# Base_Block.net
KiCad netlist of a schematic drawn in EAGLE
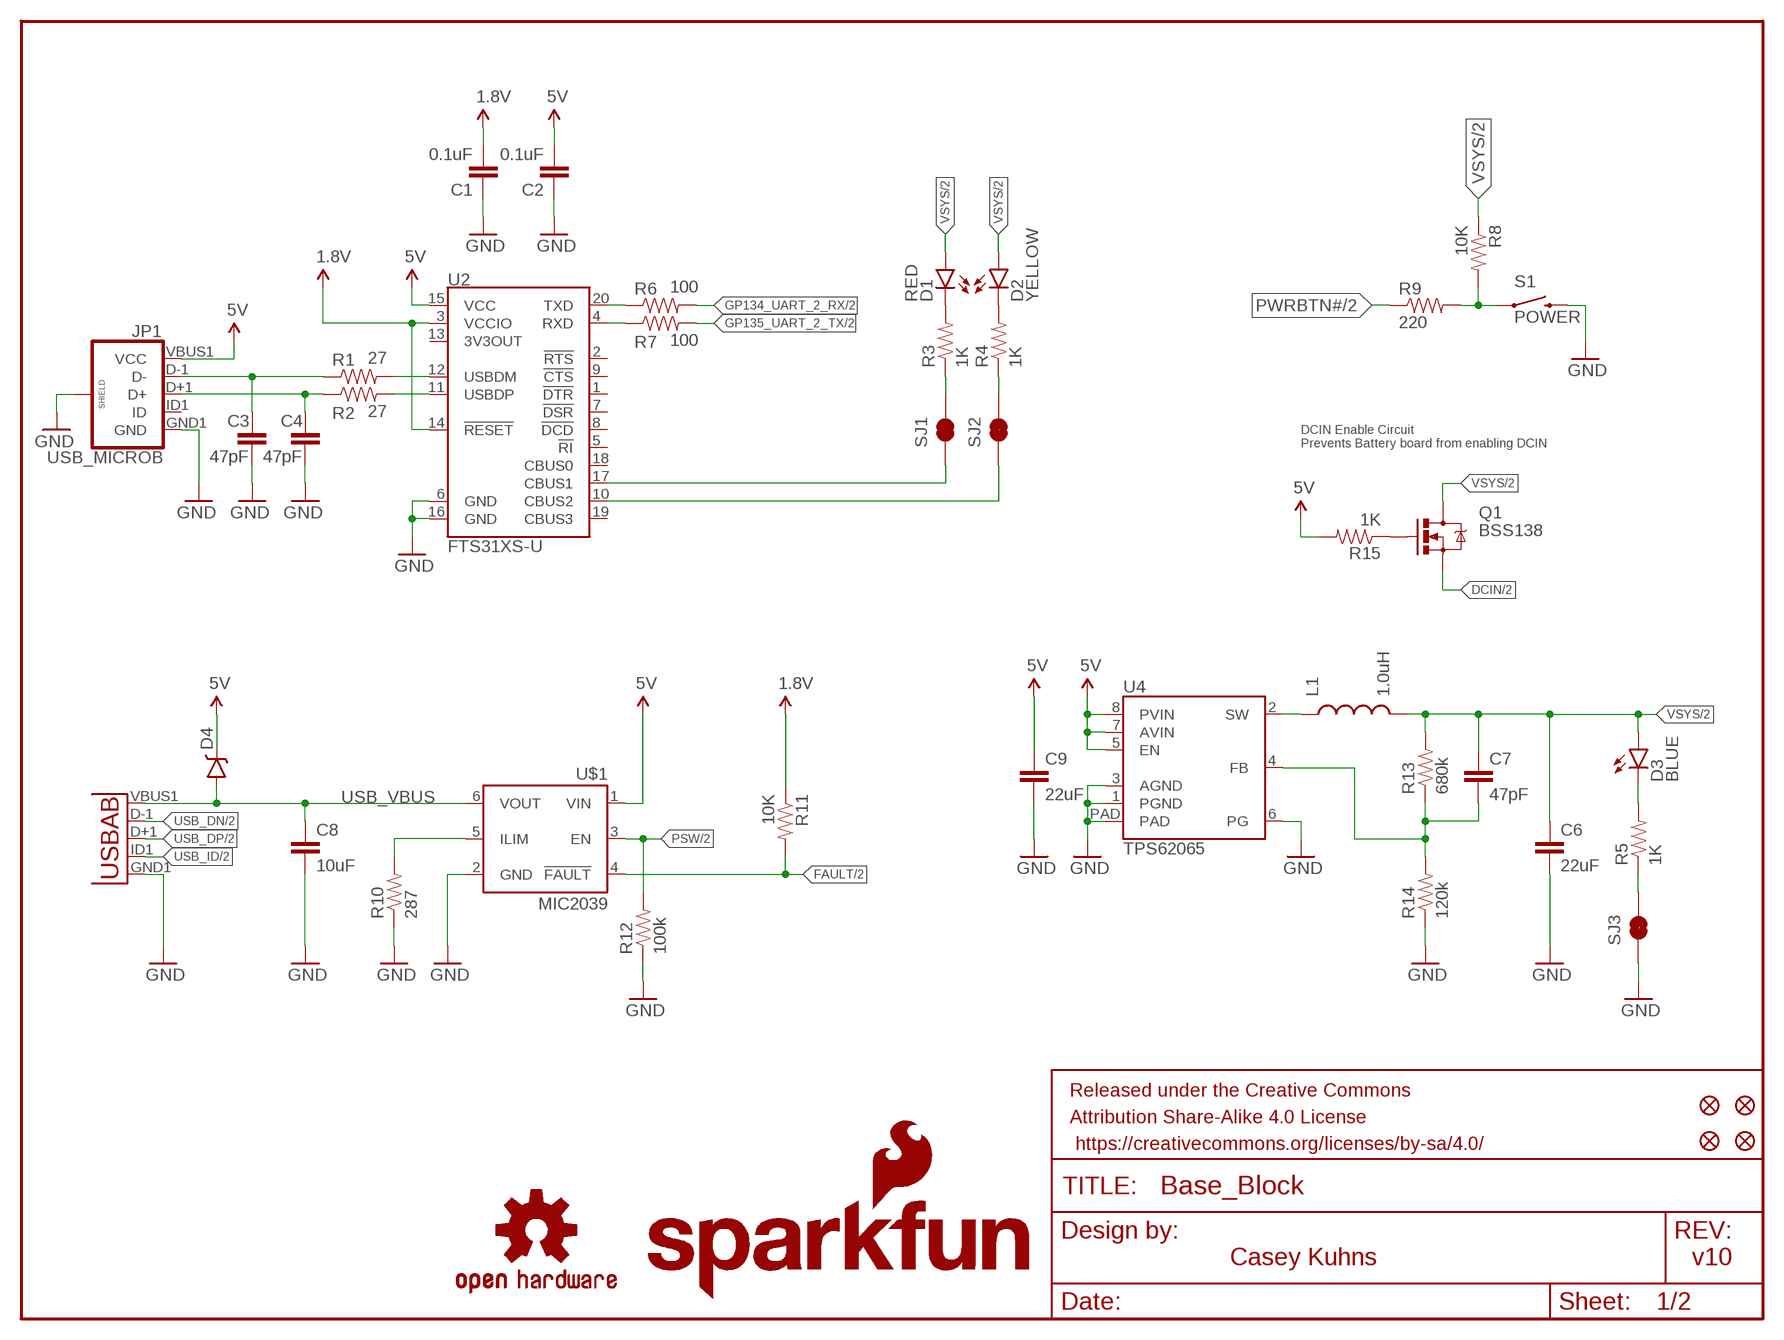
[diagram p0: schematic, sheet 1]
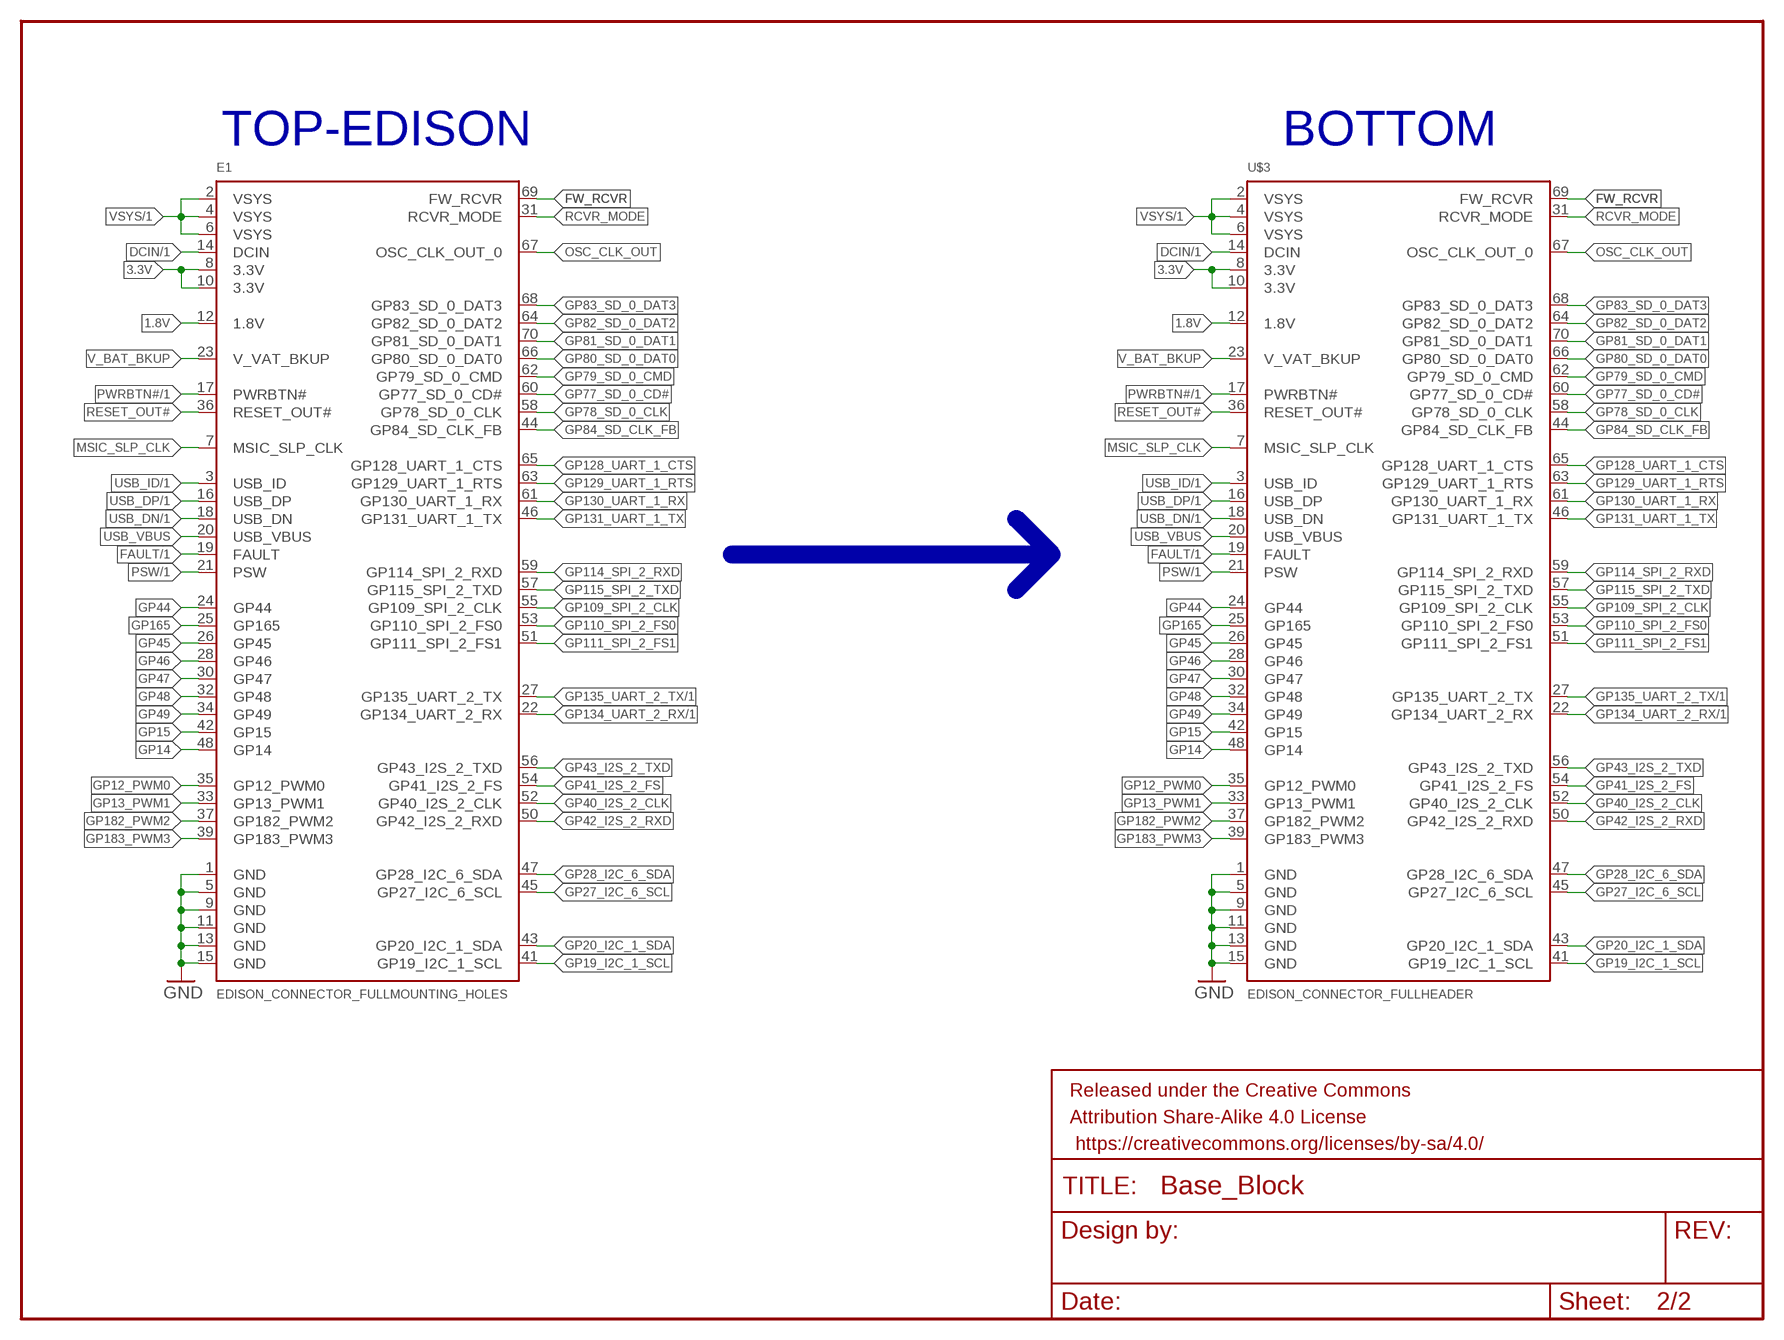
[diagram p1: schematic, sheet 2]

(export (version "E")
  (design (tool "Eeschema 10.0.6"))
  (components
    (comp (ref "C1")
      (value "0.1uF")
      (footprint "eagle-import:0603-CAP")
      (libsource (lib "eagle-import") (part "0.1UF-25V(+80/-20%)(0603)"))
    )
    (comp (ref "C2")
      (value "0.1uF")
      (footprint "eagle-import:0603-CAP")
      (libsource (lib "eagle-import") (part "0.1UF-25V(+80/-20%)(0603)"))
    )
    (comp (ref "C3")
      (value "47pF")
      (footprint "eagle-import:0603-CAP")
      (libsource (lib "eagle-import") (part "47PF-50V-5%(0603)"))
    )
    (comp (ref "C4")
      (value "47pF")
      (footprint "eagle-import:0603-CAP")
      (libsource (lib "eagle-import") (part "47PF-50V-5%(0603)"))
    )
    (comp (ref "C6")
      (value "22uF")
      (footprint "eagle-import:0805")
      (libsource (lib "eagle-import") (part "22UF-6.3V-20%(0805)"))
    )
    (comp (ref "C7")
      (value "47pF")
      (footprint "eagle-import:0603-CAP")
      (libsource (lib "eagle-import") (part "47PF-50V-5%(0603)"))
    )
    (comp (ref "C8")
      (value "10uF")
      (footprint "eagle-import:1206")
      (libsource (lib "eagle-import") (part "10UF-6.3V-20%(1206)"))
    )
    (comp (ref "C9")
      (value "22uF")
      (footprint "eagle-import:0805")
      (libsource (lib "eagle-import") (part "22UF-6.3V-20%(0805)"))
    )
    (comp (ref "D1")
      (value "RED")
      (footprint "eagle-import:LED-0603")
      (libsource (lib "eagle-import") (part "LED-RED0603"))
    )
    (comp (ref "D2")
      (value "YELLOW")
      (footprint "eagle-import:LED-0603")
      (libsource (lib "eagle-import") (part "LED-YELLOW0603"))
    )
    (comp (ref "D3")
      (value "BLUE")
      (footprint "eagle-import:LED-0603")
      (libsource (lib "eagle-import") (part "LED-BLUE0603"))
    )
    (comp (ref "D4")
      (value "DIODE-SCHOTTKY-MBRA140")
      (footprint "eagle-import:SMA-DIODE")
      (libsource (lib "eagle-import") (part "DIODE-SCHOTTKY-MBRA140"))
    )
    (comp (ref "FID1")
      (value "FIDUCIAL1X2")
      (footprint "eagle-import:FIDUCIAL-1X2")
      (libsource (lib "eagle-import") (part "FIDUCIAL1X2"))
    )
    (comp (ref "FID2")
      (value "FIDUCIAL1X2")
      (footprint "eagle-import:FIDUCIAL-1X2")
      (libsource (lib "eagle-import") (part "FIDUCIAL1X2"))
    )
    (comp (ref "FID3")
      (value "FIDUCIAL1X2")
      (footprint "eagle-import:FIDUCIAL-1X2")
      (libsource (lib "eagle-import") (part "FIDUCIAL1X2"))
    )
    (comp (ref "FID4")
      (value "FIDUCIAL1X2")
      (footprint "eagle-import:FIDUCIAL-1X2")
      (libsource (lib "eagle-import") (part "FIDUCIAL1X2"))
    )
    (comp (ref "FRAME1")
      (value "FRAME-LETTER")
      (footprint "eagle-import:CREATIVE_COMMONS")
      (libsource (lib "eagle-import") (part "FRAME-LETTER"))
    )
    (comp (ref "JP1")
      (value "USB_MICROB")
      (footprint "eagle-import:USB-B-MICRO-SMD_V03")
      (libsource (lib "eagle-import") (part "USB_MICROB_PLUGCONN-11752"))
    )
    (comp (ref "L1")
      (value "1.0uH")
      (footprint "eagle-import:INDUCTOR-SRP4020")
      (libsource (lib "eagle-import") (part "INDUCTOR"))
    )
    (comp (ref "LOGO1")
      (value "SFE_LOGO_NAME_FLAME.1_INCH")
      (footprint "eagle-import:SFE_LOGO_NAME_FLAME_.1")
      (libsource (lib "eagle-import") (part "SFE_LOGO_NAME_FLAME.1_INCH"))
    )
    (comp (ref "LOGO4")
      (value "OSHW-LOGOS")
      (footprint "eagle-import:OSHW-LOGO-S")
      (libsource (lib "eagle-import") (part "OSHW-LOGOS"))
    )
    (comp (ref "Q1")
      (value "BSS138")
      (footprint "eagle-import:SOT23-3")
      (libsource (lib "eagle-import") (part "MOSFET-NCHANNELBSS138"))
    )
    (comp (ref "R1")
      (value "27")
      (footprint "eagle-import:0603")
      (libsource (lib "eagle-import") (part "27OHM1/10W1%(0603)"))
    )
    (comp (ref "R2")
      (value "27")
      (footprint "eagle-import:0603")
      (libsource (lib "eagle-import") (part "27OHM1/10W1%(0603)"))
    )
    (comp (ref "R3")
      (value "1K")
      (footprint "eagle-import:0603-RES")
      (libsource (lib "eagle-import") (part "1KOHM1/10W1%(0603)"))
    )
    (comp (ref "R4")
      (value "1K")
      (footprint "eagle-import:0603-RES")
      (libsource (lib "eagle-import") (part "1KOHM1/10W1%(0603)"))
    )
    (comp (ref "R5")
      (value "1K")
      (footprint "eagle-import:0603-RES")
      (libsource (lib "eagle-import") (part "1KOHM1/10W1%(0603)"))
    )
    (comp (ref "R6")
      (value "100")
      (footprint "eagle-import:0603-RES")
      (libsource (lib "eagle-import") (part "100OHM1/10W1%(0603)"))
    )
    (comp (ref "R7")
      (value "100")
      (footprint "eagle-import:0603-RES")
      (libsource (lib "eagle-import") (part "100OHM1/10W1%(0603)"))
    )
    (comp (ref "R8")
      (value "10K")
      (footprint "eagle-import:0603-RES")
      (libsource (lib "eagle-import") (part "10KOHM1/10W1%(0603)0603"))
    )
    (comp (ref "R9")
      (value "220")
      (footprint "eagle-import:0603-RES")
      (libsource (lib "eagle-import") (part "22OHM1/10W1%(0603)"))
    )
    (comp (ref "R10")
      (value "287")
      (footprint "eagle-import:0603-RES")
      (libsource (lib "eagle-import") (part "287OHM-1/10W-1%(0603)"))
    )
    (comp (ref "R11")
      (value "10K")
      (footprint "eagle-import:0603-RES")
      (libsource (lib "eagle-import") (part "10KOHM1/10W1%(0603)0603"))
    )
    (comp (ref "R12")
      (value "100k")
      (footprint "eagle-import:0603-RES")
      (libsource (lib "eagle-import") (part "100KOHM1/10W1%(0603)"))
    )
    (comp (ref "R13")
      (value "680k")
      (footprint "eagle-import:0603-RES")
      (libsource (lib "eagle-import") (part "RESISTOR0603"))
    )
    (comp (ref "R14")
      (value "120k")
      (footprint "eagle-import:0603-RES")
      (libsource (lib "eagle-import") (part "RESISTOR0603"))
    )
    (comp (ref "R15")
      (value "1K")
      (footprint "eagle-import:0603-RES")
      (libsource (lib "eagle-import") (part "1KOHM1/10W1%(0603)"))
    )
    (comp (ref "S1")
      (value "POWER")
      (footprint "eagle-import:TACTILE_SWITCH-SMD-RIGHT-ANGLE")
      (libsource (lib "eagle-import") (part "SWITCH-MOMENTARY-2TACTILE-SWITCH-SMD-RIGHT-ANGLE"))
    )
    (comp (ref "SJ1")
      (value "JUMPER-PAD-2-NC_BY_TRACE")
      (footprint "eagle-import:PAD-JUMPER-2-NC_BY_TRACE_YES_SILK")
      (libsource (lib "eagle-import") (part "JUMPER-PAD-2-NC_BY_TRACE"))
    )
    (comp (ref "SJ2")
      (value "JUMPER-PAD-2-NC_BY_TRACE")
      (footprint "eagle-import:PAD-JUMPER-2-NC_BY_TRACE_YES_SILK")
      (libsource (lib "eagle-import") (part "JUMPER-PAD-2-NC_BY_TRACE"))
    )
    (comp (ref "SJ3")
      (value "JUMPER-PAD-2-NC_BY_TRACE")
      (footprint "eagle-import:PAD-JUMPER-2-NC_BY_TRACE_YES_SILK")
      (libsource (lib "eagle-import") (part "JUMPER-PAD-2-NC_BY_TRACE"))
    )
    (comp (ref "U$1")
      (value "MIC2039")
      (footprint "eagle-import:SOT23-6")
      (libsource (lib "eagle-import") (part "MIC2039"))
    )
    (comp (ref "U2")
      (value "FTS31XS-U")
      (footprint "eagle-import:SSOP20_L")
      (libsource (lib "eagle-import") (part "FT231XS"))
    )
    (comp (ref "U3")
      (value "USB-ABCONN-11794")
      (footprint "eagle-import:USB-AB-MICRO-SMD_V03")
      (libsource (lib "eagle-import") (part "USB-ABCONN-11794"))
    )
    (comp (ref "U4")
      (value "TPS62065")
      (footprint "eagle-import:WSON-8-PAD")
      (libsource (lib "eagle-import") (part "TPS62065"))
    )
    (comp (ref "E1")
      (value "EDISON_CONNECTOR_FULLMOUNTING_HOLES")
      (footprint "eagle-import:EDISON_DAUGHTER")
      (libsource (lib "eagle-import") (part "EDISON_CONNECTOR_FULLMOUNTING_HOLES"))
    )
    (comp (ref "FRAME2")
      (value "FRAME-LETTER")
      (footprint "eagle-import:CREATIVE_COMMONS")
      (libsource (lib "eagle-import") (part "FRAME-LETTER"))
    )
    (comp (ref "U$3")
      (value "EDISON_CONNECTOR_FULLHEADER")
      (footprint "eagle-import:DF40C-70DP-0.4(51)")
      (libsource (lib "eagle-import") (part "EDISON_CONNECTOR_FULLHEADER"))
    )
  )
  (nets
    (net (code "1") (name "1.8V") (class "Default")
      (node (ref "C1") (pin "2") (pinfunction "2_2") (pintype "passive"))
      (node (ref "E1") (pin "12") (pinfunction "1.8V_12") (pintype "bidirectional"))
      (node (ref "R11") (pin "1") (pinfunction "1_1") (pintype "passive"))
      (node (ref "U$3") (pin "12") (pinfunction "1.8V_12") (pintype "bidirectional"))
      (node (ref "U2") (pin "14") (pinfunction "~{RESET}_14") (pintype "bidirectional"))
      (node (ref "U2") (pin "3") (pinfunction "VCCIO_3") (pintype "bidirectional"))
    )
    (net (code "2") (name "3.3V") (class "Default")
      (node (ref "E1") (pin "10") (pinfunction "3.3V_10") (pintype "bidirectional"))
      (node (ref "E1") (pin "8") (pinfunction "3.3V_8") (pintype "bidirectional"))
      (node (ref "U$3") (pin "10") (pinfunction "3.3V_10") (pintype "bidirectional"))
      (node (ref "U$3") (pin "8") (pinfunction "3.3V_8") (pintype "bidirectional"))
    )
    (net (code "3") (name "5V") (class "Default")
      (node (ref "C2") (pin "2") (pinfunction "2_2") (pintype "passive"))
      (node (ref "C9") (pin "1") (pinfunction "1_1") (pintype "passive"))
      (node (ref "D4") (pin "C") (pinfunction "C_C") (pintype "passive"))
      (node (ref "JP1") (pin "VBUS1") (pinfunction "VCC_VBUS1") (pintype "bidirectional"))
      (node (ref "R15") (pin "2") (pinfunction "2_2") (pintype "passive"))
      (node (ref "U$1") (pin "1") (pinfunction "VIN_1") (pintype "bidirectional"))
      (node (ref "U2") (pin "15") (pinfunction "VCC_15") (pintype "bidirectional"))
      (node (ref "U4") (pin "5") (pinfunction "EN_5") (pintype "bidirectional"))
      (node (ref "U4") (pin "7") (pinfunction "AVIN_7") (pintype "bidirectional"))
      (node (ref "U4") (pin "8") (pinfunction "PVIN_8") (pintype "bidirectional"))
    )
    (net (code "4") (name "DCIN") (class "Default")
      (node (ref "E1") (pin "14") (pinfunction "DCIN_14") (pintype "bidirectional"))
      (node (ref "Q1") (pin "2") (pinfunction "S_2") (pintype "passive"))
      (node (ref "U$3") (pin "14") (pinfunction "DCIN_14") (pintype "bidirectional"))
    )
    (net (code "5") (name "FAULT") (class "Default")
      (node (ref "E1") (pin "19") (pinfunction "FAULT_19") (pintype "bidirectional"))
      (node (ref "R11") (pin "2") (pinfunction "2_2") (pintype "passive"))
      (node (ref "U$1") (pin "4") (pinfunction "~{FAULT}_4") (pintype "bidirectional"))
      (node (ref "U$3") (pin "19") (pinfunction "FAULT_19") (pintype "bidirectional"))
    )
    (net (code "6") (name "FW_RCVR") (class "Default")
      (node (ref "E1") (pin "69") (pinfunction "FW_RCVR_69") (pintype "bidirectional"))
      (node (ref "U$3") (pin "69") (pinfunction "FW_RCVR_69") (pintype "bidirectional"))
    )
    (net (code "7") (name "GND") (class "Default")
      (node (ref "C1") (pin "1") (pinfunction "1_1") (pintype "passive"))
      (node (ref "C2") (pin "1") (pinfunction "1_1") (pintype "passive"))
      (node (ref "C3") (pin "2") (pinfunction "2_2") (pintype "passive"))
      (node (ref "C4") (pin "2") (pinfunction "2_2") (pintype "passive"))
      (node (ref "C6") (pin "2") (pinfunction "2_2") (pintype "passive"))
      (node (ref "C8") (pin "2") (pinfunction "2_2") (pintype "passive"))
      (node (ref "C9") (pin "2") (pinfunction "2_2") (pintype "passive"))
      (node (ref "E1") (pin "1") (pinfunction "GND_1") (pintype "bidirectional"))
      (node (ref "E1") (pin "11") (pinfunction "GND_11") (pintype "bidirectional"))
      (node (ref "E1") (pin "13") (pinfunction "GND_13") (pintype "bidirectional"))
      (node (ref "E1") (pin "15") (pinfunction "GND_15") (pintype "bidirectional"))
      (node (ref "E1") (pin "5") (pinfunction "GND_5") (pintype "bidirectional"))
      (node (ref "E1") (pin "9") (pinfunction "GND_9") (pintype "bidirectional"))
      (node (ref "JP1") (pin "GND1") (pinfunction "GND_GND1") (pintype "bidirectional"))
      (node (ref "JP1") (pin "SHIELD1") (pinfunction "SHIELD_SHIELD1") (pintype "bidirectional"))
      (node (ref "JP1") (pin "SHIELD2") (pinfunction "SHIELD_SHIELD2") (pintype "bidirectional"))
      (node (ref "JP1") (pin "SHIELD3") (pinfunction "SHIELD_SHIELD3") (pintype "bidirectional"))
      (node (ref "R10") (pin "1") (pinfunction "1_1") (pintype "passive"))
      (node (ref "R12") (pin "1") (pinfunction "1_1") (pintype "passive"))
      (node (ref "R14") (pin "1") (pinfunction "1_1") (pintype "passive"))
      (node (ref "S1") (pin "2") (pinfunction "2_2") (pintype "passive"))
      (node (ref "SJ3") (pin "1") (pinfunction "1_1") (pintype "passive"))
      (node (ref "U$1") (pin "2") (pinfunction "GND_2") (pintype "bidirectional"))
      (node (ref "U$3") (pin "1") (pinfunction "GND_1") (pintype "bidirectional"))
      (node (ref "U$3") (pin "11") (pinfunction "GND_11") (pintype "bidirectional"))
      (node (ref "U$3") (pin "13") (pinfunction "GND_13") (pintype "bidirectional"))
      (node (ref "U$3") (pin "15") (pinfunction "GND_15") (pintype "bidirectional"))
      (node (ref "U$3") (pin "5") (pinfunction "GND_5") (pintype "bidirectional"))
      (node (ref "U$3") (pin "9") (pinfunction "GND_9") (pintype "bidirectional"))
      (node (ref "U2") (pin "16") (pinfunction "GND_16") (pintype "bidirectional"))
      (node (ref "U2") (pin "6") (pinfunction "GND_6") (pintype "bidirectional"))
      (node (ref "U3") (pin "GND1") (pinfunction "GND_GND1") (pintype "bidirectional"))
      (node (ref "U4") (pin "1") (pinfunction "PGND_1") (pintype "bidirectional"))
      (node (ref "U4") (pin "3") (pinfunction "AGND_3") (pintype "bidirectional"))
      (node (ref "U4") (pin "6") (pinfunction "PG_6") (pintype "bidirectional"))
      (node (ref "U4") (pin "PAD") (pinfunction "PAD_PAD") (pintype "bidirectional"))
    )
    (net (code "8") (name "GP12_PWM0") (class "Default")
      (node (ref "E1") (pin "35") (pinfunction "GP12_PWM0_35") (pintype "bidirectional"))
      (node (ref "U$3") (pin "35") (pinfunction "GP12_PWM0_35") (pintype "bidirectional"))
    )
    (net (code "9") (name "GP13_PWM1") (class "Default")
      (node (ref "E1") (pin "33") (pinfunction "GP13_PWM1_33") (pintype "bidirectional"))
      (node (ref "U$3") (pin "33") (pinfunction "GP13_PWM1_33") (pintype "bidirectional"))
    )
    (net (code "10") (name "GP14") (class "Default")
      (node (ref "E1") (pin "48") (pinfunction "GP14_48") (pintype "bidirectional"))
      (node (ref "U$3") (pin "48") (pinfunction "GP14_48") (pintype "bidirectional"))
    )
    (net (code "11") (name "GP15") (class "Default")
      (node (ref "E1") (pin "42") (pinfunction "GP15_42") (pintype "bidirectional"))
      (node (ref "U$3") (pin "42") (pinfunction "GP15_42") (pintype "bidirectional"))
    )
    (net (code "12") (name "GP19_I2C_1_SCL") (class "Default")
      (node (ref "E1") (pin "41") (pinfunction "GP19_I2C_1_SCL_41") (pintype "bidirectional"))
      (node (ref "U$3") (pin "41") (pinfunction "GP19_I2C_1_SCL_41") (pintype "bidirectional"))
    )
    (net (code "13") (name "GP20_I2C_1_SDA") (class "Default")
      (node (ref "E1") (pin "43") (pinfunction "GP20_I2C_1_SDA_43") (pintype "bidirectional"))
      (node (ref "U$3") (pin "43") (pinfunction "GP20_I2C_1_SDA_43") (pintype "bidirectional"))
    )
    (net (code "14") (name "GP27_I2C_6_SCL") (class "Default")
      (node (ref "E1") (pin "45") (pinfunction "GP27_I2C_6_SCL_45") (pintype "bidirectional"))
      (node (ref "U$3") (pin "45") (pinfunction "GP27_I2C_6_SCL_45") (pintype "bidirectional"))
    )
    (net (code "15") (name "GP28_I2C_6_SDA") (class "Default")
      (node (ref "E1") (pin "47") (pinfunction "GP28_I2C_6_SDA_47") (pintype "bidirectional"))
      (node (ref "U$3") (pin "47") (pinfunction "GP28_I2C_6_SDA_47") (pintype "bidirectional"))
    )
    (net (code "16") (name "GP40_I2S_2_CLK") (class "Default")
      (node (ref "E1") (pin "52") (pinfunction "GP40_I2S_2_CLK_52") (pintype "bidirectional"))
      (node (ref "U$3") (pin "52") (pinfunction "GP40_I2S_2_CLK_52") (pintype "bidirectional"))
    )
    (net (code "17") (name "GP41_I2S_2_FS") (class "Default")
      (node (ref "E1") (pin "54") (pinfunction "GP41_I2S_2_FS_54") (pintype "bidirectional"))
      (node (ref "U$3") (pin "54") (pinfunction "GP41_I2S_2_FS_54") (pintype "bidirectional"))
    )
    (net (code "18") (name "GP42_I2S_2_RXD") (class "Default")
      (node (ref "E1") (pin "50") (pinfunction "GP42_I2S_2_RXD_50") (pintype "bidirectional"))
      (node (ref "U$3") (pin "50") (pinfunction "GP42_I2S_2_RXD_50") (pintype "bidirectional"))
    )
    (net (code "19") (name "GP43_I2S_2_TXD") (class "Default")
      (node (ref "E1") (pin "56") (pinfunction "GP43_I2S_2_TXD_56") (pintype "bidirectional"))
      (node (ref "U$3") (pin "56") (pinfunction "GP43_I2S_2_TXD_56") (pintype "bidirectional"))
    )
    (net (code "20") (name "GP44") (class "Default")
      (node (ref "E1") (pin "24") (pinfunction "GP44_24") (pintype "bidirectional"))
      (node (ref "U$3") (pin "24") (pinfunction "GP44_24") (pintype "bidirectional"))
    )
    (net (code "21") (name "GP45") (class "Default")
      (node (ref "E1") (pin "26") (pinfunction "GP45_26") (pintype "bidirectional"))
      (node (ref "U$3") (pin "26") (pinfunction "GP45_26") (pintype "bidirectional"))
    )
    (net (code "22") (name "GP46") (class "Default")
      (node (ref "E1") (pin "28") (pinfunction "GP46_28") (pintype "bidirectional"))
      (node (ref "U$3") (pin "28") (pinfunction "GP46_28") (pintype "bidirectional"))
    )
    (net (code "23") (name "GP47") (class "Default")
      (node (ref "E1") (pin "30") (pinfunction "GP47_30") (pintype "bidirectional"))
      (node (ref "U$3") (pin "30") (pinfunction "GP47_30") (pintype "bidirectional"))
    )
    (net (code "24") (name "GP48") (class "Default")
      (node (ref "E1") (pin "32") (pinfunction "GP48_32") (pintype "bidirectional"))
      (node (ref "U$3") (pin "32") (pinfunction "GP48_32") (pintype "bidirectional"))
    )
    (net (code "25") (name "GP49") (class "Default")
      (node (ref "E1") (pin "34") (pinfunction "GP49_34") (pintype "bidirectional"))
      (node (ref "U$3") (pin "34") (pinfunction "GP49_34") (pintype "bidirectional"))
    )
    (net (code "26") (name "GP77_SD_0_CD#") (class "Default")
      (node (ref "E1") (pin "60") (pinfunction "GP77_SD_0_CD#_60") (pintype "bidirectional"))
      (node (ref "U$3") (pin "60") (pinfunction "GP77_SD_0_CD#_60") (pintype "bidirectional"))
    )
    (net (code "27") (name "GP78_SD_0_CLK") (class "Default")
      (node (ref "E1") (pin "58") (pinfunction "GP78_SD_0_CLK_58") (pintype "bidirectional"))
      (node (ref "U$3") (pin "58") (pinfunction "GP78_SD_0_CLK_58") (pintype "bidirectional"))
    )
    (net (code "28") (name "GP79_SD_0_CMD") (class "Default")
      (node (ref "E1") (pin "62") (pinfunction "GP79_SD_0_CMD_62") (pintype "bidirectional"))
      (node (ref "U$3") (pin "62") (pinfunction "GP79_SD_0_CMD_62") (pintype "bidirectional"))
    )
    (net (code "29") (name "GP80_SD_0_DAT0") (class "Default")
      (node (ref "E1") (pin "66") (pinfunction "GP80_SD_0_DAT0_66") (pintype "bidirectional"))
      (node (ref "U$3") (pin "66") (pinfunction "GP80_SD_0_DAT0_66") (pintype "bidirectional"))
    )
    (net (code "30") (name "GP81_SD_0_DAT1") (class "Default")
      (node (ref "E1") (pin "70") (pinfunction "GP81_SD_0_DAT1_70") (pintype "bidirectional"))
      (node (ref "U$3") (pin "70") (pinfunction "GP81_SD_0_DAT1_70") (pintype "bidirectional"))
    )
    (net (code "31") (name "GP82_SD_0_DAT2") (class "Default")
      (node (ref "E1") (pin "64") (pinfunction "GP82_SD_0_DAT2_64") (pintype "bidirectional"))
      (node (ref "U$3") (pin "64") (pinfunction "GP82_SD_0_DAT2_64") (pintype "bidirectional"))
    )
    (net (code "32") (name "GP83_SD_0_DAT3") (class "Default")
      (node (ref "E1") (pin "68") (pinfunction "GP83_SD_0_DAT3_68") (pintype "bidirectional"))
      (node (ref "U$3") (pin "68") (pinfunction "GP83_SD_0_DAT3_68") (pintype "bidirectional"))
    )
    (net (code "33") (name "GP84_SD_CLK_FB") (class "Default")
      (node (ref "E1") (pin "44") (pinfunction "GP84_SD_CLK_FB_44") (pintype "bidirectional"))
      (node (ref "U$3") (pin "44") (pinfunction "GP84_SD_CLK_FB_44") (pintype "bidirectional"))
    )
    (net (code "34") (name "GP109_SPI_2_CLK") (class "Default")
      (node (ref "E1") (pin "55") (pinfunction "GP109_SPI_2_CLK_55") (pintype "bidirectional"))
      (node (ref "U$3") (pin "55") (pinfunction "GP109_SPI_2_CLK_55") (pintype "bidirectional"))
    )
    (net (code "35") (name "GP110_SPI_2_FS0") (class "Default")
      (node (ref "E1") (pin "53") (pinfunction "GP110_SPI_2_FS0_53") (pintype "bidirectional"))
      (node (ref "U$3") (pin "53") (pinfunction "GP110_SPI_2_FS0_53") (pintype "bidirectional"))
    )
    (net (code "36") (name "GP111_SPI_2_FS1") (class "Default")
      (node (ref "E1") (pin "51") (pinfunction "GP111_SPI_2_FS1_51") (pintype "bidirectional"))
      (node (ref "U$3") (pin "51") (pinfunction "GP111_SPI_2_FS1_51") (pintype "bidirectional"))
    )
    (net (code "37") (name "GP114_SPI_2_RXD") (class "Default")
      (node (ref "E1") (pin "59") (pinfunction "GP114_SPI_2_RXD_59") (pintype "bidirectional"))
      (node (ref "U$3") (pin "59") (pinfunction "GP114_SPI_2_RXD_59") (pintype "bidirectional"))
    )
    (net (code "38") (name "GP115_SPI_2_TXD") (class "Default")
      (node (ref "E1") (pin "57") (pinfunction "GP115_SPI_2_TXD_57") (pintype "bidirectional"))
      (node (ref "U$3") (pin "57") (pinfunction "GP115_SPI_2_TXD_57") (pintype "bidirectional"))
    )
    (net (code "39") (name "GP128_UART_1_CTS") (class "Default")
      (node (ref "E1") (pin "65") (pinfunction "GP128_UART_1_CTS_65") (pintype "bidirectional"))
      (node (ref "U$3") (pin "65") (pinfunction "GP128_UART_1_CTS_65") (pintype "bidirectional"))
    )
    (net (code "40") (name "GP129_UART_1_RTS") (class "Default")
      (node (ref "E1") (pin "63") (pinfunction "GP129_UART_1_RTS_63") (pintype "bidirectional"))
      (node (ref "U$3") (pin "63") (pinfunction "GP129_UART_1_RTS_63") (pintype "bidirectional"))
    )
    (net (code "41") (name "GP130_UART_1_RX") (class "Default")
      (node (ref "E1") (pin "61") (pinfunction "GP130_UART_1_RX_61") (pintype "bidirectional"))
      (node (ref "U$3") (pin "61") (pinfunction "GP130_UART_1_RX_61") (pintype "bidirectional"))
    )
    (net (code "42") (name "GP131_UART_1_TX") (class "Default")
      (node (ref "E1") (pin "46") (pinfunction "GP131_UART_1_TX_46") (pintype "bidirectional"))
      (node (ref "U$3") (pin "46") (pinfunction "GP131_UART_1_TX_46") (pintype "bidirectional"))
    )
    (net (code "43") (name "GP134_UART_2_RX") (class "Default")
      (node (ref "E1") (pin "22") (pinfunction "GP134_UART_2_RX_22") (pintype "bidirectional"))
      (node (ref "R6") (pin "2") (pinfunction "2_2") (pintype "passive"))
      (node (ref "U$3") (pin "22") (pinfunction "GP134_UART_2_RX_22") (pintype "bidirectional"))
    )
    (net (code "44") (name "GP135_UART_2_TX") (class "Default")
      (node (ref "E1") (pin "27") (pinfunction "GP135_UART_2_TX_27") (pintype "bidirectional"))
      (node (ref "R7") (pin "2") (pinfunction "2_2") (pintype "passive"))
      (node (ref "U$3") (pin "27") (pinfunction "GP135_UART_2_TX_27") (pintype "bidirectional"))
    )
    (net (code "45") (name "GP165") (class "Default")
      (node (ref "E1") (pin "25") (pinfunction "GP165_25") (pintype "bidirectional"))
      (node (ref "U$3") (pin "25") (pinfunction "GP165_25") (pintype "bidirectional"))
    )
    (net (code "46") (name "GP182_PWM2") (class "Default")
      (node (ref "E1") (pin "37") (pinfunction "GP182_PWM2_37") (pintype "bidirectional"))
      (node (ref "U$3") (pin "37") (pinfunction "GP182_PWM2_37") (pintype "bidirectional"))
    )
    (net (code "47") (name "GP183_PWM3") (class "Default")
      (node (ref "E1") (pin "39") (pinfunction "GP183_PWM3_39") (pintype "bidirectional"))
      (node (ref "U$3") (pin "39") (pinfunction "GP183_PWM3_39") (pintype "bidirectional"))
    )
    (net (code "48") (name "MSIC_SLP_CLK") (class "Default")
      (node (ref "E1") (pin "7") (pinfunction "MSIC_SLP_CLK_7") (pintype "bidirectional"))
      (node (ref "U$3") (pin "7") (pinfunction "MSIC_SLP_CLK_7") (pintype "bidirectional"))
    )
    (net (code "49") (name "Net-(D1-PadC)") (class "Default")
      (node (ref "D1") (pin "C") (pinfunction "C_C") (pintype "passive"))
      (node (ref "R3") (pin "2") (pinfunction "2_2") (pintype "passive"))
    )
    (net (code "50") (name "Net-(D2-PadC)") (class "Default")
      (node (ref "D2") (pin "C") (pinfunction "C_C") (pintype "passive"))
      (node (ref "R4") (pin "2") (pinfunction "2_2") (pintype "passive"))
    )
    (net (code "51") (name "Net-(D3-PadC)") (class "Default")
      (node (ref "D3") (pin "C") (pinfunction "C_C") (pintype "passive"))
      (node (ref "R5") (pin "2") (pinfunction "2_2") (pintype "passive"))
    )
    (net (code "52") (name "Net-(JP1-D+)") (class "Default")
      (node (ref "C4") (pin "1") (pinfunction "1_1") (pintype "passive"))
      (node (ref "JP1") (pin "D+1") (pinfunction "D+_D+1") (pintype "bidirectional"))
      (node (ref "R2") (pin "1") (pinfunction "1_1") (pintype "passive"))
    )
    (net (code "53") (name "Net-(JP1-D-)") (class "Default")
      (node (ref "C3") (pin "1") (pinfunction "1_1") (pintype "passive"))
      (node (ref "JP1") (pin "D-1") (pinfunction "D-_D-1") (pintype "bidirectional"))
      (node (ref "R1") (pin "1") (pinfunction "1_1") (pintype "passive"))
    )
    (net (code "54") (name "Net-(L1-1)") (class "Default")
      (node (ref "L1") (pin "P$1") (pinfunction "1_P$1") (pintype "passive"))
      (node (ref "U4") (pin "2") (pinfunction "SW_2") (pintype "bidirectional"))
    )
    (net (code "55") (name "Net-(Q1-G)") (class "Default")
      (node (ref "Q1") (pin "1") (pinfunction "G_1") (pintype "passive"))
      (node (ref "R15") (pin "1") (pinfunction "1_1") (pintype "passive"))
    )
    (net (code "56") (name "Net-(R3-Pad1)") (class "Default")
      (node (ref "R3") (pin "1") (pinfunction "1_1") (pintype "passive"))
      (node (ref "SJ1") (pin "2") (pinfunction "2_2") (pintype "passive"))
    )
    (net (code "57") (name "Net-(R4-Pad1)") (class "Default")
      (node (ref "R4") (pin "1") (pinfunction "1_1") (pintype "passive"))
      (node (ref "SJ2") (pin "2") (pinfunction "2_2") (pintype "passive"))
    )
    (net (code "58") (name "Net-(R5-Pad1)") (class "Default")
      (node (ref "R5") (pin "1") (pinfunction "1_1") (pintype "passive"))
      (node (ref "SJ3") (pin "2") (pinfunction "2_2") (pintype "passive"))
    )
    (net (code "59") (name "Net-(R8-Pad2)") (class "Default")
      (node (ref "R8") (pin "2") (pinfunction "2_2") (pintype "passive"))
      (node (ref "R9") (pin "2") (pinfunction "2_2") (pintype "passive"))
      (node (ref "S1") (pin "1") (pinfunction "1_1") (pintype "passive"))
    )
    (net (code "60") (name "Net-(U$1-ILIM)") (class "Default")
      (node (ref "R10") (pin "2") (pinfunction "2_2") (pintype "passive"))
      (node (ref "U$1") (pin "5") (pinfunction "ILIM_5") (pintype "bidirectional"))
    )
    (net (code "61") (name "Net-(U2-CBUS1)") (class "Default")
      (node (ref "SJ1") (pin "1") (pinfunction "1_1") (pintype "passive"))
      (node (ref "U2") (pin "17") (pinfunction "CBUS1_17") (pintype "bidirectional"))
    )
    (net (code "62") (name "Net-(U2-CBUS2)") (class "Default")
      (node (ref "SJ2") (pin "1") (pinfunction "1_1") (pintype "passive"))
      (node (ref "U2") (pin "10") (pinfunction "CBUS2_10") (pintype "bidirectional"))
    )
    (net (code "63") (name "Net-(U2-RXD)") (class "Default")
      (node (ref "R7") (pin "1") (pinfunction "1_1") (pintype "passive"))
      (node (ref "U2") (pin "4") (pinfunction "RXD_4") (pintype "bidirectional"))
    )
    (net (code "64") (name "Net-(U2-TXD)") (class "Default")
      (node (ref "R6") (pin "1") (pinfunction "1_1") (pintype "passive"))
      (node (ref "U2") (pin "20") (pinfunction "TXD_20") (pintype "bidirectional"))
    )
    (net (code "65") (name "Net-(U2-USBDM)") (class "Default")
      (node (ref "R1") (pin "2") (pinfunction "2_2") (pintype "passive"))
      (node (ref "U2") (pin "12") (pinfunction "USBDM_12") (pintype "bidirectional"))
    )
    (net (code "66") (name "Net-(U2-USBDP)") (class "Default")
      (node (ref "R2") (pin "2") (pinfunction "2_2") (pintype "passive"))
      (node (ref "U2") (pin "11") (pinfunction "USBDP_11") (pintype "bidirectional"))
    )
    (net (code "67") (name "Net-(U4-FB)") (class "Default")
      (node (ref "C7") (pin "2") (pinfunction "2_2") (pintype "passive"))
      (node (ref "R13") (pin "1") (pinfunction "1_1") (pintype "passive"))
      (node (ref "R14") (pin "2") (pinfunction "2_2") (pintype "passive"))
      (node (ref "U4") (pin "4") (pinfunction "FB_4") (pintype "bidirectional"))
    )
    (net (code "68") (name "OSC_CLK_OUT") (class "Default")
      (node (ref "E1") (pin "67") (pinfunction "OSC_CLK_OUT_0_67") (pintype "bidirectional"))
      (node (ref "U$3") (pin "67") (pinfunction "OSC_CLK_OUT_0_67") (pintype "bidirectional"))
    )
    (net (code "69") (name "PSW") (class "Default")
      (node (ref "E1") (pin "21") (pinfunction "PSW_21") (pintype "bidirectional"))
      (node (ref "R12") (pin "2") (pinfunction "2_2") (pintype "passive"))
      (node (ref "U$1") (pin "3") (pinfunction "EN_3") (pintype "bidirectional"))
      (node (ref "U$3") (pin "21") (pinfunction "PSW_21") (pintype "bidirectional"))
    )
    (net (code "70") (name "PWRBTN#") (class "Default")
      (node (ref "E1") (pin "17") (pinfunction "PWRBTN#_17") (pintype "bidirectional"))
      (node (ref "R9") (pin "1") (pinfunction "1_1") (pintype "passive"))
      (node (ref "U$3") (pin "17") (pinfunction "PWRBTN#_17") (pintype "bidirectional"))
    )
    (net (code "71") (name "RCVR_MODE") (class "Default")
      (node (ref "E1") (pin "31") (pinfunction "RCVR_MODE_31") (pintype "bidirectional"))
      (node (ref "U$3") (pin "31") (pinfunction "RCVR_MODE_31") (pintype "bidirectional"))
    )
    (net (code "72") (name "RESET_OUT#") (class "Default")
      (node (ref "E1") (pin "36") (pinfunction "RESET_OUT#_36") (pintype "bidirectional"))
      (node (ref "U$3") (pin "36") (pinfunction "RESET_OUT#_36") (pintype "bidirectional"))
    )
    (net (code "73") (name "USB_DN") (class "Default")
      (node (ref "E1") (pin "18") (pinfunction "USB_DN_18") (pintype "bidirectional"))
      (node (ref "U$3") (pin "18") (pinfunction "USB_DN_18") (pintype "bidirectional"))
      (node (ref "U3") (pin "D-1") (pinfunction "D-_D-1") (pintype "bidirectional"))
    )
    (net (code "74") (name "USB_DP") (class "Default")
      (node (ref "E1") (pin "16") (pinfunction "USB_DP_16") (pintype "bidirectional"))
      (node (ref "U$3") (pin "16") (pinfunction "USB_DP_16") (pintype "bidirectional"))
      (node (ref "U3") (pin "D+1") (pinfunction "D+_D+1") (pintype "bidirectional"))
    )
    (net (code "75") (name "USB_ID") (class "Default")
      (node (ref "E1") (pin "3") (pinfunction "USB_ID_3") (pintype "bidirectional"))
      (node (ref "U$3") (pin "3") (pinfunction "USB_ID_3") (pintype "bidirectional"))
      (node (ref "U3") (pin "ID1") (pinfunction "USBID_ID1") (pintype "bidirectional"))
    )
    (net (code "76") (name "USB_VBUS") (class "Default")
      (node (ref "C8") (pin "1") (pinfunction "1_1") (pintype "passive"))
      (node (ref "D4") (pin "A") (pinfunction "A_A") (pintype "passive"))
      (node (ref "E1") (pin "20") (pinfunction "USB_VBUS_20") (pintype "bidirectional"))
      (node (ref "U$1") (pin "6") (pinfunction "VOUT_6") (pintype "bidirectional"))
      (node (ref "U$3") (pin "20") (pinfunction "USB_VBUS_20") (pintype "bidirectional"))
      (node (ref "U3") (pin "VBUS1") (pinfunction "VBUS_VBUS1") (pintype "bidirectional"))
    )
    (net (code "77") (name "VSYS") (class "Default")
      (node (ref "C6") (pin "1") (pinfunction "1_1") (pintype "passive"))
      (node (ref "C7") (pin "1") (pinfunction "1_1") (pintype "passive"))
      (node (ref "D1") (pin "A") (pinfunction "A_A") (pintype "passive"))
      (node (ref "D2") (pin "A") (pinfunction "A_A") (pintype "passive"))
      (node (ref "D3") (pin "A") (pinfunction "A_A") (pintype "passive"))
      (node (ref "E1") (pin "2") (pinfunction "VSYS_2") (pintype "bidirectional"))
      (node (ref "E1") (pin "4") (pinfunction "VSYS_4") (pintype "bidirectional"))
      (node (ref "E1") (pin "6") (pinfunction "VSYS_6") (pintype "bidirectional"))
      (node (ref "L1") (pin "P$2") (pinfunction "2_P$2") (pintype "passive"))
      (node (ref "Q1") (pin "3") (pinfunction "D_3") (pintype "passive"))
      (node (ref "R13") (pin "2") (pinfunction "2_2") (pintype "passive"))
      (node (ref "R8") (pin "1") (pinfunction "1_1") (pintype "passive"))
      (node (ref "U$3") (pin "2") (pinfunction "VSYS_2") (pintype "bidirectional"))
      (node (ref "U$3") (pin "4") (pinfunction "VSYS_4") (pintype "bidirectional"))
      (node (ref "U$3") (pin "6") (pinfunction "VSYS_6") (pintype "bidirectional"))
    )
    (net (code "78") (name "V_BAT_BKUP") (class "Default")
      (node (ref "E1") (pin "23") (pinfunction "V_VAT_BKUP_23") (pintype "bidirectional"))
      (node (ref "U$3") (pin "23") (pinfunction "V_VAT_BKUP_23") (pintype "bidirectional"))
    )
    (net (code "79") (name "unconnected-(JP1-ID-PadID1)") (class "Default")
      (node (ref "JP1") (pin "ID1") (pinfunction "ID_ID1") (pintype "bidirectional"))
    )
    (net (code "80") (name "unconnected-(U2-3V3OUT-Pad13)") (class "Default")
      (node (ref "U2") (pin "13") (pinfunction "3V3OUT_13") (pintype "bidirectional"))
    )
    (net (code "81") (name "unconnected-(U2-CBUS0-Pad18)") (class "Default")
      (node (ref "U2") (pin "18") (pinfunction "CBUS0_18") (pintype "bidirectional"))
    )
    (net (code "82") (name "unconnected-(U2-CBUS3-Pad19)") (class "Default")
      (node (ref "U2") (pin "19") (pinfunction "CBUS3_19") (pintype "bidirectional"))
    )
    (net (code "83") (name "unconnected-(U2-~{CTS}-Pad9)") (class "Default")
      (node (ref "U2") (pin "9") (pinfunction "~{CTS}_9") (pintype "bidirectional"))
    )
    (net (code "84") (name "unconnected-(U2-~{DCD}-Pad8)") (class "Default")
      (node (ref "U2") (pin "8") (pinfunction "~{DCD}_8") (pintype "bidirectional"))
    )
    (net (code "85") (name "unconnected-(U2-~{DSR}-Pad7)") (class "Default")
      (node (ref "U2") (pin "7") (pinfunction "~{DSR}_7") (pintype "bidirectional"))
    )
    (net (code "86") (name "unconnected-(U2-~{DTR}-Pad1)") (class "Default")
      (node (ref "U2") (pin "1") (pinfunction "~{DTR}_1") (pintype "bidirectional"))
    )
    (net (code "87") (name "unconnected-(U2-~{RI}-Pad5)") (class "Default")
      (node (ref "U2") (pin "5") (pinfunction "~{RI}_5") (pintype "bidirectional"))
    )
    (net (code "88") (name "unconnected-(U2-~{RTS}-Pad2)") (class "Default")
      (node (ref "U2") (pin "2") (pinfunction "~{RTS}_2") (pintype "bidirectional"))
    )
  )
)
